# ampli_piezo.net
KiCad netlist of a schematic drawn in EAGLE
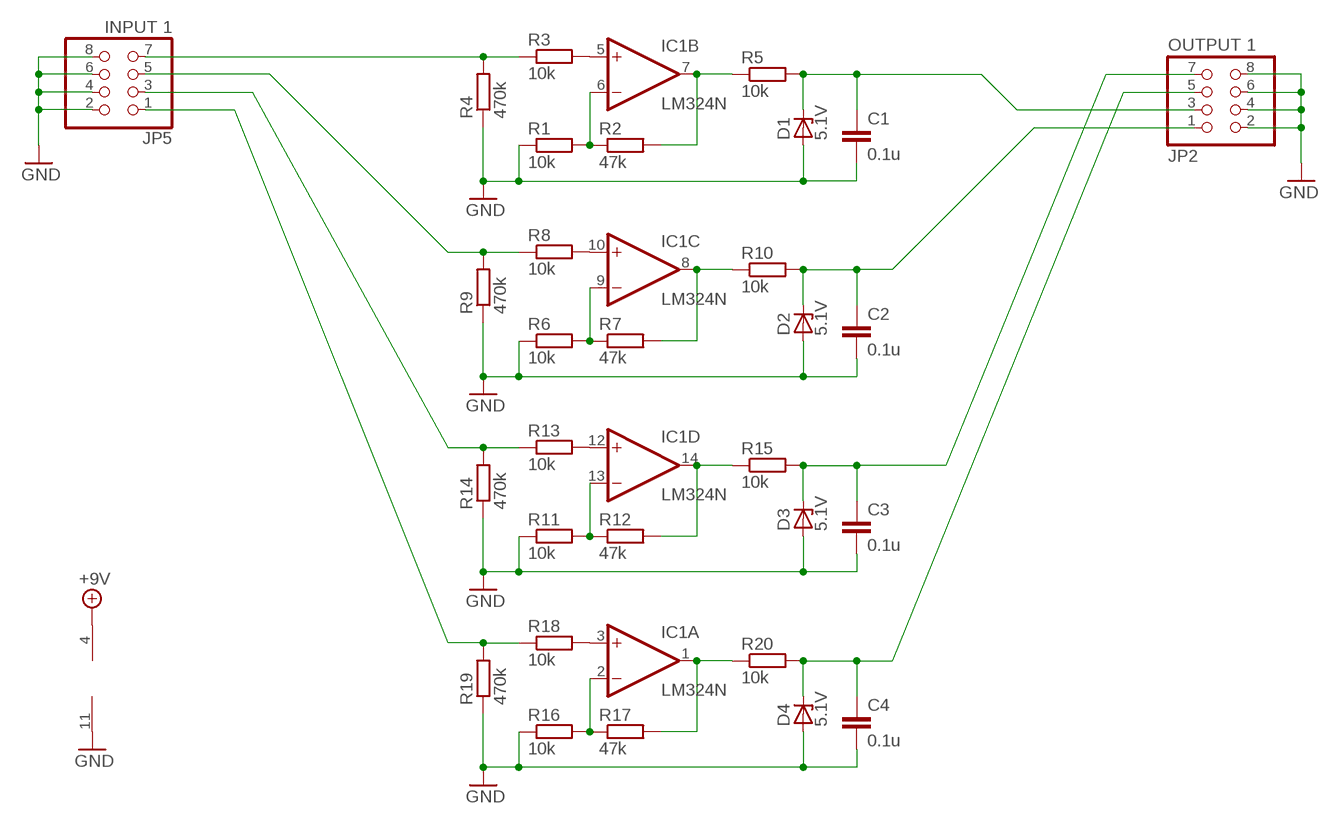
[diagram p0: schematic, sheet 1]

(export (version "E")
  (design (tool "Eeschema 10.0.6"))
  (components
    (comp (ref "C1")
      (value "0.1u")
      (footprint "eagle-import:C050-025X075")
      (libsource (lib "eagle-import") (part "C-EU050-025X075"))
    )
    (comp (ref "C2")
      (value "0.1u")
      (footprint "eagle-import:C050-025X075")
      (libsource (lib "eagle-import") (part "C-EU050-025X075"))
    )
    (comp (ref "C3")
      (value "0.1u")
      (footprint "eagle-import:C050-025X075")
      (libsource (lib "eagle-import") (part "C-EU050-025X075"))
    )
    (comp (ref "C4")
      (value "0.1u")
      (footprint "eagle-import:C050-025X075")
      (libsource (lib "eagle-import") (part "C-EU050-025X075"))
    )
    (comp (ref "D1")
      (value "5.1V")
      (footprint "eagle-import:DO35Z10")
      (libsource (lib "eagle-import") (part "ZENER-DIODEDO35Z10"))
    )
    (comp (ref "D2")
      (value "5.1V")
      (footprint "eagle-import:DO35Z10")
      (libsource (lib "eagle-import") (part "ZENER-DIODEDO35Z10"))
    )
    (comp (ref "D3")
      (value "5.1V")
      (footprint "eagle-import:DO35Z10")
      (libsource (lib "eagle-import") (part "ZENER-DIODEDO35Z10"))
    )
    (comp (ref "D4")
      (value "5.1V")
      (footprint "eagle-import:DO35Z10")
      (libsource (lib "eagle-import") (part "ZENER-DIODEDO35Z10"))
    )
    (comp (ref "IC1")
      (value "LM324N")
      (footprint "eagle-import:DIL14")
      (libsource (lib "eagle-import") (part "LM324N"))
    )
    (comp (ref "JP2")
      (value "OUTPUT 1")
      (footprint "eagle-import:2X04_90")
      (libsource (lib "eagle-import") (part "PINHD-2X4/90"))
    )
    (comp (ref "JP5")
      (value "INPUT 1")
      (footprint "eagle-import:2X04_90")
      (libsource (lib "eagle-import") (part "PINHD-2X4/90"))
    )
    (comp (ref "R1")
      (value "10k")
      (footprint "eagle-import:0207_10")
      (libsource (lib "eagle-import") (part "R-EU_0207/10"))
    )
    (comp (ref "R2")
      (value "47k")
      (footprint "eagle-import:0207_10")
      (libsource (lib "eagle-import") (part "R-EU_0207/10"))
    )
    (comp (ref "R3")
      (value "10k")
      (footprint "eagle-import:0207_10")
      (libsource (lib "eagle-import") (part "R-EU_0207/10"))
    )
    (comp (ref "R4")
      (value "470k")
      (footprint "eagle-import:0207_10")
      (libsource (lib "eagle-import") (part "R-EU_0207/10"))
    )
    (comp (ref "R5")
      (value "10k")
      (footprint "eagle-import:0207_10")
      (libsource (lib "eagle-import") (part "R-EU_0207/10"))
    )
    (comp (ref "R6")
      (value "10k")
      (footprint "eagle-import:0207_10")
      (libsource (lib "eagle-import") (part "R-EU_0207/10"))
    )
    (comp (ref "R7")
      (value "47k")
      (footprint "eagle-import:0207_10")
      (libsource (lib "eagle-import") (part "R-EU_0207/10"))
    )
    (comp (ref "R8")
      (value "10k")
      (footprint "eagle-import:0207_10")
      (libsource (lib "eagle-import") (part "R-EU_0207/10"))
    )
    (comp (ref "R9")
      (value "470k")
      (footprint "eagle-import:0207_10")
      (libsource (lib "eagle-import") (part "R-EU_0207/10"))
    )
    (comp (ref "R10")
      (value "10k")
      (footprint "eagle-import:0207_10")
      (libsource (lib "eagle-import") (part "R-EU_0207/10"))
    )
    (comp (ref "R11")
      (value "10k")
      (footprint "eagle-import:0207_10")
      (libsource (lib "eagle-import") (part "R-EU_0207/10"))
    )
    (comp (ref "R12")
      (value "47k")
      (footprint "eagle-import:0207_10")
      (libsource (lib "eagle-import") (part "R-EU_0207/10"))
    )
    (comp (ref "R13")
      (value "10k")
      (footprint "eagle-import:0207_10")
      (libsource (lib "eagle-import") (part "R-EU_0207/10"))
    )
    (comp (ref "R14")
      (value "470k")
      (footprint "eagle-import:0207_10")
      (libsource (lib "eagle-import") (part "R-EU_0207/10"))
    )
    (comp (ref "R15")
      (value "10k")
      (footprint "eagle-import:0207_10")
      (libsource (lib "eagle-import") (part "R-EU_0207/10"))
    )
    (comp (ref "R16")
      (value "10k")
      (footprint "eagle-import:0207_10")
      (libsource (lib "eagle-import") (part "R-EU_0207/10"))
    )
    (comp (ref "R17")
      (value "47k")
      (footprint "eagle-import:0207_10")
      (libsource (lib "eagle-import") (part "R-EU_0207/10"))
    )
    (comp (ref "R18")
      (value "10k")
      (footprint "eagle-import:0207_10")
      (libsource (lib "eagle-import") (part "R-EU_0207/10"))
    )
    (comp (ref "R19")
      (value "470k")
      (footprint "eagle-import:0207_10")
      (libsource (lib "eagle-import") (part "R-EU_0207/10"))
    )
    (comp (ref "R20")
      (value "10k")
      (footprint "eagle-import:0207_10")
      (libsource (lib "eagle-import") (part "R-EU_0207/10"))
    )
  )
  (nets
    (net (code "1") (name "+9V") (class "Default")
      (node (ref "IC1") (pin "4") (pinfunction "V+_4") (pintype "power_in"))
    )
    (net (code "2") (name "GND") (class "Default")
      (node (ref "C1") (pin "2") (pinfunction "2_2") (pintype "passive"))
      (node (ref "C2") (pin "2") (pinfunction "2_2") (pintype "passive"))
      (node (ref "C3") (pin "2") (pinfunction "2_2") (pintype "passive"))
      (node (ref "C4") (pin "2") (pinfunction "2_2") (pintype "passive"))
      (node (ref "D1") (pin "A") (pinfunction "A_A") (pintype "passive"))
      (node (ref "D2") (pin "A") (pinfunction "A_A") (pintype "passive"))
      (node (ref "D3") (pin "A") (pinfunction "A_A") (pintype "passive"))
      (node (ref "D4") (pin "A") (pinfunction "A_A") (pintype "passive"))
      (node (ref "IC1") (pin "11") (pinfunction "V-_11") (pintype "power_in"))
      (node (ref "JP2") (pin "2") (pinfunction "2_2") (pintype "passive"))
      (node (ref "JP2") (pin "4") (pinfunction "4_4") (pintype "passive"))
      (node (ref "JP2") (pin "6") (pinfunction "6_6") (pintype "passive"))
      (node (ref "JP2") (pin "8") (pinfunction "8_8") (pintype "passive"))
      (node (ref "JP5") (pin "2") (pinfunction "2_2") (pintype "passive"))
      (node (ref "JP5") (pin "4") (pinfunction "4_4") (pintype "passive"))
      (node (ref "JP5") (pin "6") (pinfunction "6_6") (pintype "passive"))
      (node (ref "JP5") (pin "8") (pinfunction "8_8") (pintype "passive"))
      (node (ref "R1") (pin "1") (pinfunction "1_1") (pintype "passive"))
      (node (ref "R11") (pin "1") (pinfunction "1_1") (pintype "passive"))
      (node (ref "R14") (pin "1") (pinfunction "1_1") (pintype "passive"))
      (node (ref "R16") (pin "1") (pinfunction "1_1") (pintype "passive"))
      (node (ref "R19") (pin "1") (pinfunction "1_1") (pintype "passive"))
      (node (ref "R4") (pin "1") (pinfunction "1_1") (pintype "passive"))
      (node (ref "R6") (pin "1") (pinfunction "1_1") (pintype "passive"))
      (node (ref "R9") (pin "1") (pinfunction "1_1") (pintype "passive"))
    )
    (net (code "3") (name "Net-(C1-Pad1)") (class "Default")
      (node (ref "C1") (pin "1") (pinfunction "1_1") (pintype "passive"))
      (node (ref "D1") (pin "C") (pinfunction "C_C") (pintype "passive"))
      (node (ref "JP2") (pin "3") (pinfunction "3_3") (pintype "passive"))
      (node (ref "R5") (pin "2") (pinfunction "2_2") (pintype "passive"))
    )
    (net (code "4") (name "Net-(C2-Pad1)") (class "Default")
      (node (ref "C2") (pin "1") (pinfunction "1_1") (pintype "passive"))
      (node (ref "D2") (pin "C") (pinfunction "C_C") (pintype "passive"))
      (node (ref "JP2") (pin "1") (pinfunction "1_1") (pintype "passive"))
      (node (ref "R10") (pin "2") (pinfunction "2_2") (pintype "passive"))
    )
    (net (code "5") (name "Net-(C3-Pad1)") (class "Default")
      (node (ref "C3") (pin "1") (pinfunction "1_1") (pintype "passive"))
      (node (ref "D3") (pin "C") (pinfunction "C_C") (pintype "passive"))
      (node (ref "JP2") (pin "7") (pinfunction "7_7") (pintype "passive"))
      (node (ref "R15") (pin "2") (pinfunction "2_2") (pintype "passive"))
    )
    (net (code "6") (name "Net-(C4-Pad1)") (class "Default")
      (node (ref "C4") (pin "1") (pinfunction "1_1") (pintype "passive"))
      (node (ref "D4") (pin "C") (pinfunction "C_C") (pintype "passive"))
      (node (ref "JP2") (pin "5") (pinfunction "5_5") (pintype "passive"))
      (node (ref "R20") (pin "2") (pinfunction "2_2") (pintype "passive"))
    )
    (net (code "7") (name "Net-(IC1A-+IN)") (class "Default")
      (node (ref "IC1") (pin "3") (pinfunction "+IN_3") (pintype "input"))
      (node (ref "R18") (pin "2") (pinfunction "2_2") (pintype "passive"))
    )
    (net (code "8") (name "Net-(IC1A--IN)") (class "Default")
      (node (ref "IC1") (pin "2") (pinfunction "-IN_2") (pintype "input"))
      (node (ref "R16") (pin "2") (pinfunction "2_2") (pintype "passive"))
      (node (ref "R17") (pin "1") (pinfunction "1_1") (pintype "passive"))
    )
    (net (code "9") (name "Net-(IC1A-OUT)") (class "Default")
      (node (ref "IC1") (pin "1") (pinfunction "OUT_1") (pintype "output"))
      (node (ref "R17") (pin "2") (pinfunction "2_2") (pintype "passive"))
      (node (ref "R20") (pin "1") (pinfunction "1_1") (pintype "passive"))
    )
    (net (code "10") (name "Net-(IC1B-+IN)") (class "Default")
      (node (ref "IC1") (pin "5") (pinfunction "+IN_5") (pintype "input"))
      (node (ref "R3") (pin "2") (pinfunction "2_2") (pintype "passive"))
    )
    (net (code "11") (name "Net-(IC1B--IN)") (class "Default")
      (node (ref "IC1") (pin "6") (pinfunction "-IN_6") (pintype "input"))
      (node (ref "R1") (pin "2") (pinfunction "2_2") (pintype "passive"))
      (node (ref "R2") (pin "1") (pinfunction "1_1") (pintype "passive"))
    )
    (net (code "12") (name "Net-(IC1B-OUT)") (class "Default")
      (node (ref "IC1") (pin "7") (pinfunction "OUT_7") (pintype "output"))
      (node (ref "R2") (pin "2") (pinfunction "2_2") (pintype "passive"))
      (node (ref "R5") (pin "1") (pinfunction "1_1") (pintype "passive"))
    )
    (net (code "13") (name "Net-(IC1C-+IN)") (class "Default")
      (node (ref "IC1") (pin "10") (pinfunction "+IN_10") (pintype "input"))
      (node (ref "R8") (pin "2") (pinfunction "2_2") (pintype "passive"))
    )
    (net (code "14") (name "Net-(IC1C--IN)") (class "Default")
      (node (ref "IC1") (pin "9") (pinfunction "-IN_9") (pintype "input"))
      (node (ref "R6") (pin "2") (pinfunction "2_2") (pintype "passive"))
      (node (ref "R7") (pin "1") (pinfunction "1_1") (pintype "passive"))
    )
    (net (code "15") (name "Net-(IC1C-OUT)") (class "Default")
      (node (ref "IC1") (pin "8") (pinfunction "OUT_8") (pintype "output"))
      (node (ref "R10") (pin "1") (pinfunction "1_1") (pintype "passive"))
      (node (ref "R7") (pin "2") (pinfunction "2_2") (pintype "passive"))
    )
    (net (code "16") (name "Net-(IC1D-+IN)") (class "Default")
      (node (ref "IC1") (pin "12") (pinfunction "+IN_12") (pintype "input"))
      (node (ref "R13") (pin "2") (pinfunction "2_2") (pintype "passive"))
    )
    (net (code "17") (name "Net-(IC1D--IN)") (class "Default")
      (node (ref "IC1") (pin "13") (pinfunction "-IN_13") (pintype "input"))
      (node (ref "R11") (pin "2") (pinfunction "2_2") (pintype "passive"))
      (node (ref "R12") (pin "1") (pinfunction "1_1") (pintype "passive"))
    )
    (net (code "18") (name "Net-(IC1D-OUT)") (class "Default")
      (node (ref "IC1") (pin "14") (pinfunction "OUT_14") (pintype "output"))
      (node (ref "R12") (pin "2") (pinfunction "2_2") (pintype "passive"))
      (node (ref "R15") (pin "1") (pinfunction "1_1") (pintype "passive"))
    )
    (net (code "19") (name "Net-(JP5-Pad1)") (class "Default")
      (node (ref "JP5") (pin "1") (pinfunction "1_1") (pintype "passive"))
      (node (ref "R18") (pin "1") (pinfunction "1_1") (pintype "passive"))
      (node (ref "R19") (pin "2") (pinfunction "2_2") (pintype "passive"))
    )
    (net (code "20") (name "Net-(JP5-Pad3)") (class "Default")
      (node (ref "JP5") (pin "3") (pinfunction "3_3") (pintype "passive"))
      (node (ref "R13") (pin "1") (pinfunction "1_1") (pintype "passive"))
      (node (ref "R14") (pin "2") (pinfunction "2_2") (pintype "passive"))
    )
    (net (code "21") (name "Net-(JP5-Pad5)") (class "Default")
      (node (ref "JP5") (pin "5") (pinfunction "5_5") (pintype "passive"))
      (node (ref "R8") (pin "1") (pinfunction "1_1") (pintype "passive"))
      (node (ref "R9") (pin "2") (pinfunction "2_2") (pintype "passive"))
    )
    (net (code "22") (name "Net-(JP5-Pad7)") (class "Default")
      (node (ref "JP5") (pin "7") (pinfunction "7_7") (pintype "passive"))
      (node (ref "R3") (pin "1") (pinfunction "1_1") (pintype "passive"))
      (node (ref "R4") (pin "2") (pinfunction "2_2") (pintype "passive"))
    )
  )
)
